# AS3364_DG412_bus_mixer_v1_4.net
KiCad netlist of a schematic drawn in EAGLE
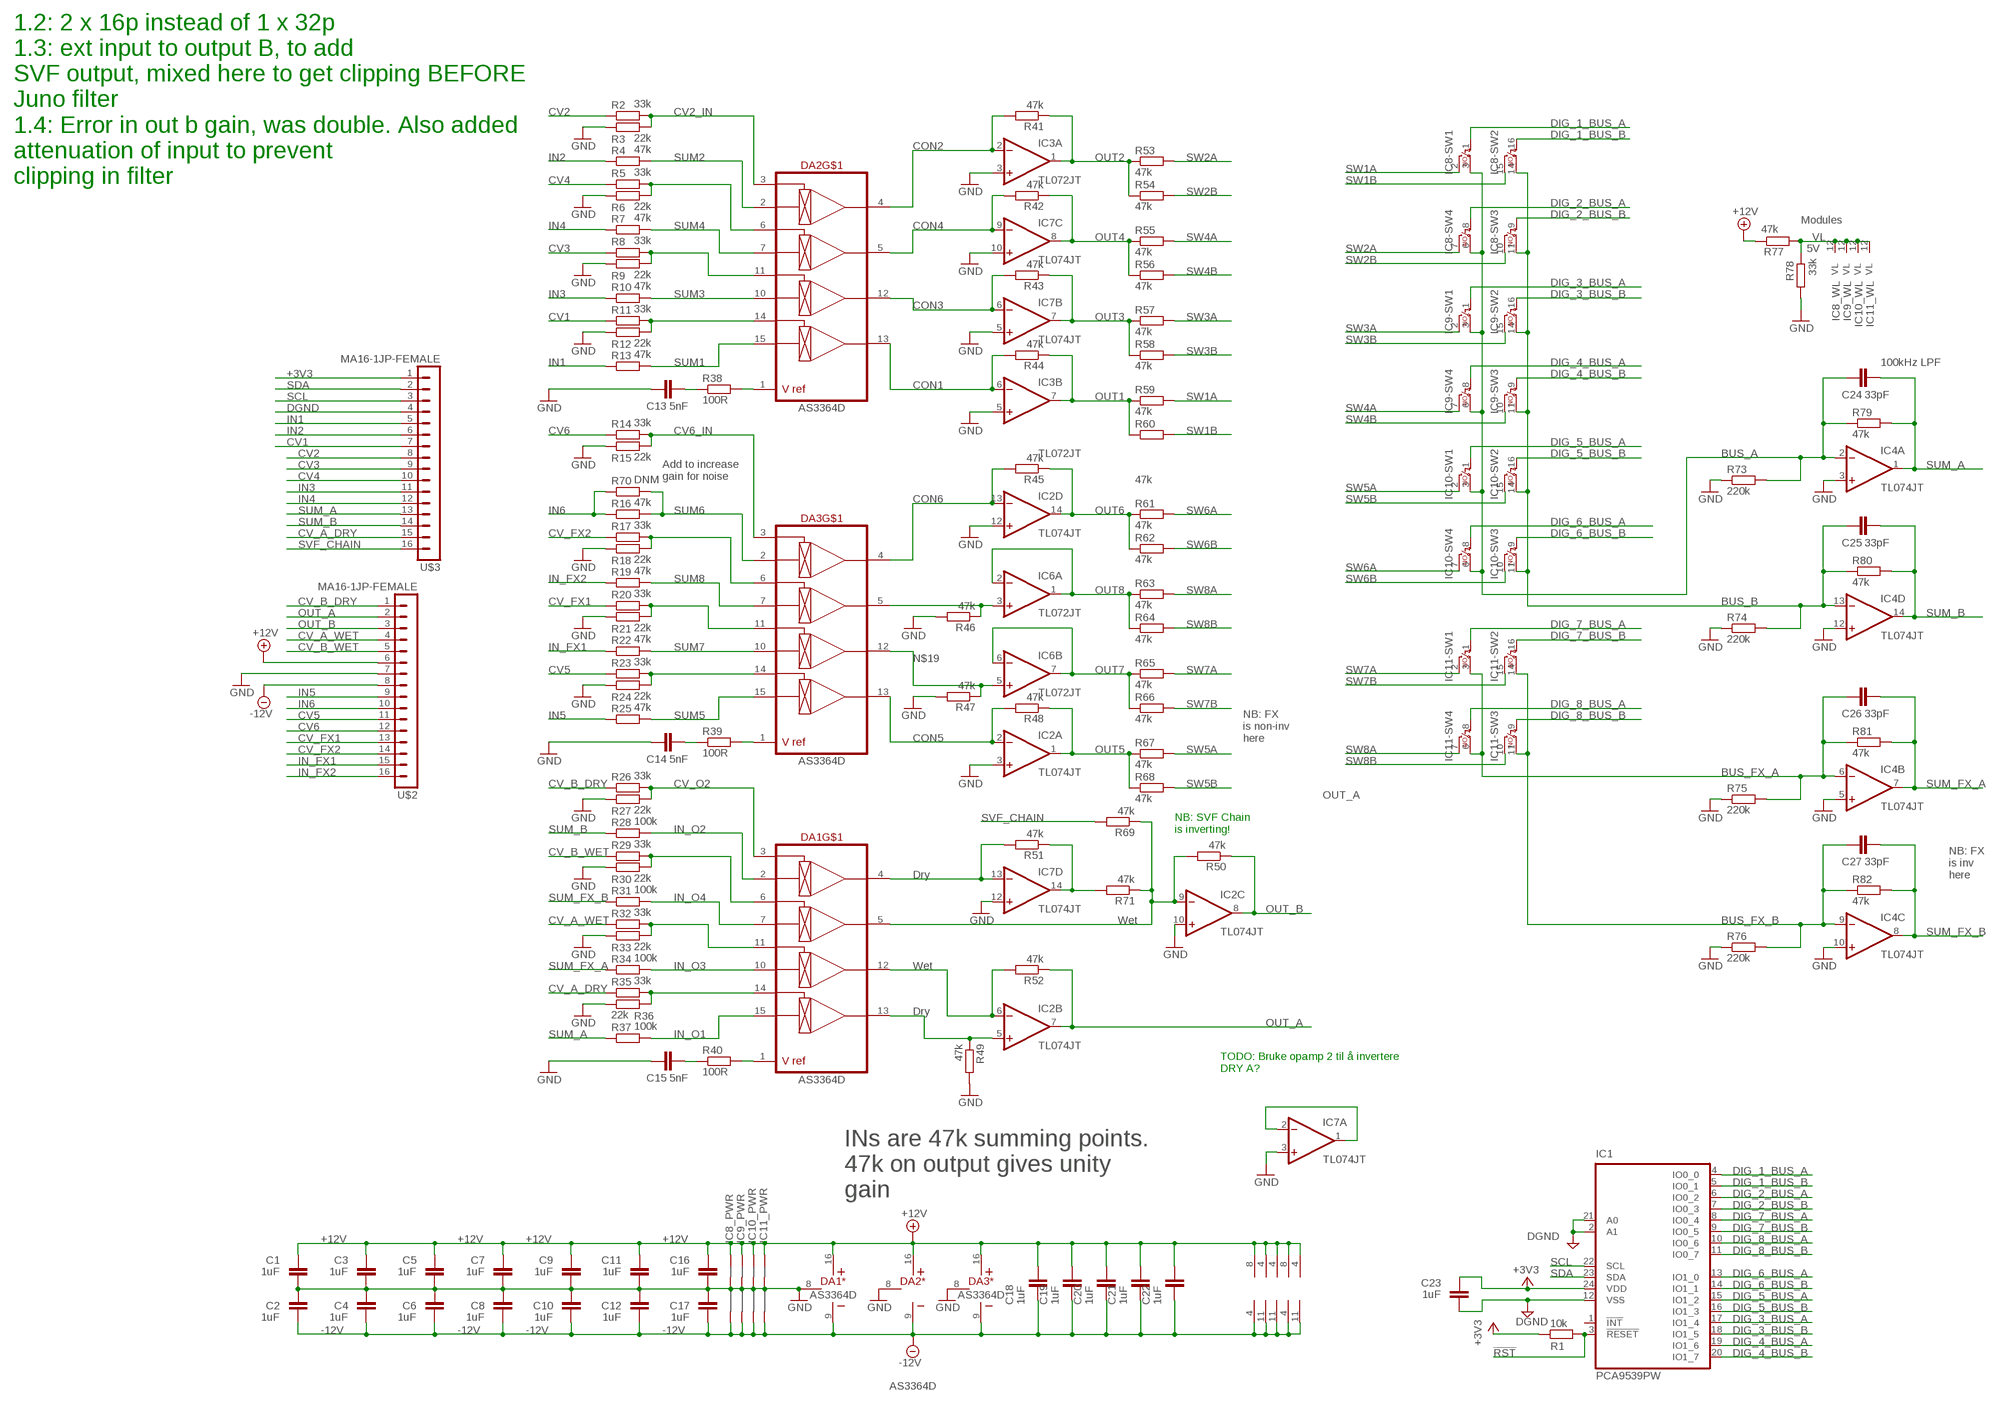
[diagram p0: schematic, sheet 1]

(export (version "E")
  (design (tool "Eeschema 10.0.6"))
  (components
    (comp (ref "C1")
      (value "1uF")
      (footprint "eagle-import:C0402-J")
      (libsource (lib "eagle-import") (part "C-EU-J0402"))
    )
    (comp (ref "C2")
      (value "1uF")
      (footprint "eagle-import:C0402-J")
      (libsource (lib "eagle-import") (part "C-EU-J0402"))
    )
    (comp (ref "C3")
      (value "1uF")
      (footprint "eagle-import:C0402-J")
      (libsource (lib "eagle-import") (part "C-EU-J0402"))
    )
    (comp (ref "C4")
      (value "1uF")
      (footprint "eagle-import:C0402-J")
      (libsource (lib "eagle-import") (part "C-EU-J0402"))
    )
    (comp (ref "C5")
      (value "1uF")
      (footprint "eagle-import:C0402-J")
      (libsource (lib "eagle-import") (part "C-EU-J0402"))
    )
    (comp (ref "C6")
      (value "1uF")
      (footprint "eagle-import:C0402-J")
      (libsource (lib "eagle-import") (part "C-EU-J0402"))
    )
    (comp (ref "C7")
      (value "1uF")
      (footprint "eagle-import:C0402-J")
      (libsource (lib "eagle-import") (part "C-EU-J0402"))
    )
    (comp (ref "C8")
      (value "1uF")
      (footprint "eagle-import:C0402-J")
      (libsource (lib "eagle-import") (part "C-EU-J0402"))
    )
    (comp (ref "C9")
      (value "1uF")
      (footprint "eagle-import:C0402-J")
      (libsource (lib "eagle-import") (part "C-EU-J0402"))
    )
    (comp (ref "C10")
      (value "1uF")
      (footprint "eagle-import:C0402-J")
      (libsource (lib "eagle-import") (part "C-EU-J0402"))
    )
    (comp (ref "C11")
      (value "1uF")
      (footprint "eagle-import:C0402-J")
      (libsource (lib "eagle-import") (part "C-EU-J0402"))
    )
    (comp (ref "C12")
      (value "1uF")
      (footprint "eagle-import:C0402-J")
      (libsource (lib "eagle-import") (part "C-EU-J0402"))
    )
    (comp (ref "C13")
      (value "5nF")
      (footprint "eagle-import:C0402-J")
      (libsource (lib "eagle-import") (part "C-EU-J0402"))
    )
    (comp (ref "C14")
      (value "5nF")
      (footprint "eagle-import:C0402-J")
      (libsource (lib "eagle-import") (part "C-EU-J0402"))
    )
    (comp (ref "C15")
      (value "5nF")
      (footprint "eagle-import:C0402-J")
      (libsource (lib "eagle-import") (part "C-EU-J0402"))
    )
    (comp (ref "C16")
      (value "1uF")
      (footprint "eagle-import:C0402-J")
      (libsource (lib "eagle-import") (part "C-EU-J0402"))
    )
    (comp (ref "C17")
      (value "1uF")
      (footprint "eagle-import:C0402-J")
      (libsource (lib "eagle-import") (part "C-EU-J0402"))
    )
    (comp (ref "C18")
      (value "1uF")
      (footprint "eagle-import:C0402")
      (libsource (lib "eagle-import") (part "C-EUC0402"))
    )
    (comp (ref "C19")
      (value "1uF")
      (footprint "eagle-import:C0402")
      (libsource (lib "eagle-import") (part "C-EUC0402"))
    )
    (comp (ref "C20")
      (value "1uF")
      (footprint "eagle-import:C0402")
      (libsource (lib "eagle-import") (part "C-EUC0402"))
    )
    (comp (ref "C21")
      (value "1uF")
      (footprint "eagle-import:C0402")
      (libsource (lib "eagle-import") (part "C-EUC0402"))
    )
    (comp (ref "C22")
      (value "1uF")
      (footprint "eagle-import:C0402")
      (libsource (lib "eagle-import") (part "C-EUC0402"))
    )
    (comp (ref "C23")
      (value "1uF")
      (footprint "eagle-import:C0402")
      (libsource (lib "eagle-import") (part "C-EUC0402"))
    )
    (comp (ref "C24")
      (value "33pF")
      (footprint "eagle-import:C0402-J")
      (libsource (lib "eagle-import") (part "C-EU-J0402"))
    )
    (comp (ref "C25")
      (value "33pF")
      (footprint "eagle-import:C0402-J")
      (libsource (lib "eagle-import") (part "C-EU-J0402"))
    )
    (comp (ref "C26")
      (value "33pF")
      (footprint "eagle-import:C0402-J")
      (libsource (lib "eagle-import") (part "C-EU-J0402"))
    )
    (comp (ref "C27")
      (value "33pF")
      (footprint "eagle-import:C0402-J")
      (libsource (lib "eagle-import") (part "C-EU-J0402"))
    )
    (comp (ref "DA1")
      (value "AS3364D")
      (footprint "eagle-import:DIL16J")
      (libsource (lib "eagle-import") (part "AS3364D"))
    )
    (comp (ref "DA2")
      (value "AS3364D")
      (footprint "eagle-import:DIL16J")
      (libsource (lib "eagle-import") (part "AS3364D"))
    )
    (comp (ref "DA3")
      (value "AS3364D")
      (footprint "eagle-import:DIL16J")
      (libsource (lib "eagle-import") (part "AS3364D"))
    )
    (comp (ref "IC1")
      (value "PCA9539PW")
      (footprint "eagle-import:TSSOP24J")
      (libsource (lib "eagle-import") (part "PCA9539PW"))
    )
    (comp (ref "IC2")
      (value "TL074JT")
      (footprint "eagle-import:TSSOP14J")
      (libsource (lib "eagle-import") (part "TL074JT"))
    )
    (comp (ref "IC3")
      (value "TL072JT")
      (footprint "eagle-import:TSSOP8J")
      (libsource (lib "eagle-import") (part "TL072JT"))
    )
    (comp (ref "IC4")
      (value "TL074JT")
      (footprint "eagle-import:TSSOP14J")
      (libsource (lib "eagle-import") (part "TL074JT"))
    )
    (comp (ref "IC6")
      (value "TL072JT")
      (footprint "eagle-import:TSSOP8J")
      (libsource (lib "eagle-import") (part "TL072JT"))
    )
    (comp (ref "IC7")
      (value "TL074JT")
      (footprint "eagle-import:TSSOP14J")
      (libsource (lib "eagle-import") (part "TL074JT"))
    )
    (comp (ref "IC8")
      (value "DG412-J")
      (footprint "eagle-import:DIL16J")
      (libsource (lib "eagle-import") (part "DG412-J"))
    )
    (comp (ref "IC9")
      (value "DG412-J")
      (footprint "eagle-import:DIL16J")
      (libsource (lib "eagle-import") (part "DG412-J"))
    )
    (comp (ref "IC10")
      (value "DG412-J")
      (footprint "eagle-import:DIL16J")
      (libsource (lib "eagle-import") (part "DG412-J"))
    )
    (comp (ref "IC11")
      (value "DG412-J")
      (footprint "eagle-import:DIL16J")
      (libsource (lib "eagle-import") (part "DG412-J"))
    )
    (comp (ref "R1")
      (value "10k")
      (footprint "eagle-import:R0402")
      (libsource (lib "eagle-import") (part "R-EU_R0402"))
    )
    (comp (ref "R2")
      (value "33k")
      (footprint "eagle-import:R0402")
      (libsource (lib "eagle-import") (part "R-EU_R0402"))
    )
    (comp (ref "R3")
      (value "22k")
      (footprint "eagle-import:R0402")
      (libsource (lib "eagle-import") (part "R-EU_R0402"))
    )
    (comp (ref "R4")
      (value "47k")
      (footprint "eagle-import:R0402")
      (libsource (lib "eagle-import") (part "R-EU_R0402"))
    )
    (comp (ref "R5")
      (value "33k")
      (footprint "eagle-import:R0402")
      (libsource (lib "eagle-import") (part "R-EU_R0402"))
    )
    (comp (ref "R6")
      (value "22k")
      (footprint "eagle-import:R0402")
      (libsource (lib "eagle-import") (part "R-EU_R0402"))
    )
    (comp (ref "R7")
      (value "47k")
      (footprint "eagle-import:R0402")
      (libsource (lib "eagle-import") (part "R-EU_R0402"))
    )
    (comp (ref "R8")
      (value "33k")
      (footprint "eagle-import:R0402")
      (libsource (lib "eagle-import") (part "R-EU_R0402"))
    )
    (comp (ref "R9")
      (value "22k")
      (footprint "eagle-import:R0402")
      (libsource (lib "eagle-import") (part "R-EU_R0402"))
    )
    (comp (ref "R10")
      (value "47k")
      (footprint "eagle-import:R0402")
      (libsource (lib "eagle-import") (part "R-EU_R0402"))
    )
    (comp (ref "R11")
      (value "33k")
      (footprint "eagle-import:R0402")
      (libsource (lib "eagle-import") (part "R-EU_R0402"))
    )
    (comp (ref "R12")
      (value "22k")
      (footprint "eagle-import:R0402")
      (libsource (lib "eagle-import") (part "R-EU_R0402"))
    )
    (comp (ref "R13")
      (value "47k")
      (footprint "eagle-import:R0402")
      (libsource (lib "eagle-import") (part "R-EU_R0402"))
    )
    (comp (ref "R14")
      (value "33k")
      (footprint "eagle-import:R0402")
      (libsource (lib "eagle-import") (part "R-EU_R0402"))
    )
    (comp (ref "R15")
      (value "22k")
      (footprint "eagle-import:R0402")
      (libsource (lib "eagle-import") (part "R-EU_R0402"))
    )
    (comp (ref "R16")
      (value "47k")
      (footprint "eagle-import:R0402")
      (libsource (lib "eagle-import") (part "R-EU_R0402"))
    )
    (comp (ref "R17")
      (value "33k")
      (footprint "eagle-import:R0402")
      (libsource (lib "eagle-import") (part "R-EU_R0402"))
    )
    (comp (ref "R18")
      (value "22k")
      (footprint "eagle-import:R0402")
      (libsource (lib "eagle-import") (part "R-EU_R0402"))
    )
    (comp (ref "R19")
      (value "47k")
      (footprint "eagle-import:R0402")
      (libsource (lib "eagle-import") (part "R-EU_R0402"))
    )
    (comp (ref "R20")
      (value "33k")
      (footprint "eagle-import:R0402")
      (libsource (lib "eagle-import") (part "R-EU_R0402"))
    )
    (comp (ref "R21")
      (value "22k")
      (footprint "eagle-import:R0402")
      (libsource (lib "eagle-import") (part "R-EU_R0402"))
    )
    (comp (ref "R22")
      (value "47k")
      (footprint "eagle-import:R0402")
      (libsource (lib "eagle-import") (part "R-EU_R0402"))
    )
    (comp (ref "R23")
      (value "33k")
      (footprint "eagle-import:R0402")
      (libsource (lib "eagle-import") (part "R-EU_R0402"))
    )
    (comp (ref "R24")
      (value "22k")
      (footprint "eagle-import:R0402")
      (libsource (lib "eagle-import") (part "R-EU_R0402"))
    )
    (comp (ref "R25")
      (value "47k")
      (footprint "eagle-import:R0402")
      (libsource (lib "eagle-import") (part "R-EU_R0402"))
    )
    (comp (ref "R26")
      (value "33k")
      (footprint "eagle-import:R0402")
      (libsource (lib "eagle-import") (part "R-EU_R0402"))
    )
    (comp (ref "R27")
      (value "22k")
      (footprint "eagle-import:R0402")
      (libsource (lib "eagle-import") (part "R-EU_R0402"))
    )
    (comp (ref "R28")
      (value "100k")
      (footprint "eagle-import:R0402")
      (libsource (lib "eagle-import") (part "R-EU_R0402"))
    )
    (comp (ref "R29")
      (value "33k")
      (footprint "eagle-import:R0402")
      (libsource (lib "eagle-import") (part "R-EU_R0402"))
    )
    (comp (ref "R30")
      (value "22k")
      (footprint "eagle-import:R0402")
      (libsource (lib "eagle-import") (part "R-EU_R0402"))
    )
    (comp (ref "R31")
      (value "100k")
      (footprint "eagle-import:R0402")
      (libsource (lib "eagle-import") (part "R-EU_R0402"))
    )
    (comp (ref "R32")
      (value "33k")
      (footprint "eagle-import:R0402")
      (libsource (lib "eagle-import") (part "R-EU_R0402"))
    )
    (comp (ref "R33")
      (value "22k")
      (footprint "eagle-import:R0402")
      (libsource (lib "eagle-import") (part "R-EU_R0402"))
    )
    (comp (ref "R34")
      (value "100k")
      (footprint "eagle-import:R0402")
      (libsource (lib "eagle-import") (part "R-EU_R0402"))
    )
    (comp (ref "R35")
      (value "33k")
      (footprint "eagle-import:R0402")
      (libsource (lib "eagle-import") (part "R-EU_R0402"))
    )
    (comp (ref "R36")
      (value "22k")
      (footprint "eagle-import:R0402")
      (libsource (lib "eagle-import") (part "R-EU_R0402"))
    )
    (comp (ref "R37")
      (value "100k")
      (footprint "eagle-import:R0402")
      (libsource (lib "eagle-import") (part "R-EU_R0402"))
    )
    (comp (ref "R38")
      (value "100R")
      (footprint "eagle-import:R0402")
      (libsource (lib "eagle-import") (part "R-EU_R0402"))
    )
    (comp (ref "R39")
      (value "100R")
      (footprint "eagle-import:R0402")
      (libsource (lib "eagle-import") (part "R-EU_R0402"))
    )
    (comp (ref "R40")
      (value "100R")
      (footprint "eagle-import:R0402")
      (libsource (lib "eagle-import") (part "R-EU_R0402"))
    )
    (comp (ref "R41")
      (value "47k")
      (footprint "eagle-import:R0402")
      (libsource (lib "eagle-import") (part "R-EU_R0402"))
    )
    (comp (ref "R42")
      (value "47k")
      (footprint "eagle-import:R0402")
      (libsource (lib "eagle-import") (part "R-EU_R0402"))
    )
    (comp (ref "R43")
      (value "47k")
      (footprint "eagle-import:R0402")
      (libsource (lib "eagle-import") (part "R-EU_R0402"))
    )
    (comp (ref "R44")
      (value "47k")
      (footprint "eagle-import:R0402")
      (libsource (lib "eagle-import") (part "R-EU_R0402"))
    )
    (comp (ref "R45")
      (value "47k")
      (footprint "eagle-import:R0402")
      (libsource (lib "eagle-import") (part "R-EU_R0402"))
    )
    (comp (ref "R46")
      (value "47k")
      (footprint "eagle-import:R0402")
      (libsource (lib "eagle-import") (part "R-EU_R0402"))
    )
    (comp (ref "R47")
      (value "47k")
      (footprint "eagle-import:R0402")
      (libsource (lib "eagle-import") (part "R-EU_R0402"))
    )
    (comp (ref "R48")
      (value "47k")
      (footprint "eagle-import:R0402")
      (libsource (lib "eagle-import") (part "R-EU_R0402"))
    )
    (comp (ref "R49")
      (value "47k")
      (footprint "eagle-import:R0402")
      (libsource (lib "eagle-import") (part "R-EU_R0402"))
    )
    (comp (ref "R50")
      (value "47k")
      (footprint "eagle-import:R0402")
      (libsource (lib "eagle-import") (part "R-EU_R0402"))
    )
    (comp (ref "R51")
      (value "47k")
      (footprint "eagle-import:R0402")
      (libsource (lib "eagle-import") (part "R-EU_R0402"))
    )
    (comp (ref "R52")
      (value "47k")
      (footprint "eagle-import:R0402")
      (libsource (lib "eagle-import") (part "R-EU_R0402"))
    )
    (comp (ref "R53")
      (value "47k")
      (footprint "eagle-import:R0402")
      (libsource (lib "eagle-import") (part "R-EU_R0402"))
    )
    (comp (ref "R54")
      (value "47k")
      (footprint "eagle-import:R0402")
      (libsource (lib "eagle-import") (part "R-EU_R0402"))
    )
    (comp (ref "R55")
      (value "47k")
      (footprint "eagle-import:R0402")
      (libsource (lib "eagle-import") (part "R-EU_R0402"))
    )
    (comp (ref "R56")
      (value "47k")
      (footprint "eagle-import:R0402")
      (libsource (lib "eagle-import") (part "R-EU_R0402"))
    )
    (comp (ref "R57")
      (value "47k")
      (footprint "eagle-import:R0402")
      (libsource (lib "eagle-import") (part "R-EU_R0402"))
    )
    (comp (ref "R58")
      (value "47k")
      (footprint "eagle-import:R0402")
      (libsource (lib "eagle-import") (part "R-EU_R0402"))
    )
    (comp (ref "R59")
      (value "47k")
      (footprint "eagle-import:R0402")
      (libsource (lib "eagle-import") (part "R-EU_R0402"))
    )
    (comp (ref "R60")
      (value "47k")
      (footprint "eagle-import:R0402")
      (libsource (lib "eagle-import") (part "R-EU_R0402"))
    )
    (comp (ref "R61")
      (value "47k")
      (footprint "eagle-import:R0402")
      (libsource (lib "eagle-import") (part "R-EU_R0402"))
    )
    (comp (ref "R62")
      (value "47k")
      (footprint "eagle-import:R0402")
      (libsource (lib "eagle-import") (part "R-EU_R0402"))
    )
    (comp (ref "R63")
      (value "47k")
      (footprint "eagle-import:R0402")
      (libsource (lib "eagle-import") (part "R-EU_R0402"))
    )
    (comp (ref "R64")
      (value "47k")
      (footprint "eagle-import:R0402")
      (libsource (lib "eagle-import") (part "R-EU_R0402"))
    )
    (comp (ref "R65")
      (value "47k")
      (footprint "eagle-import:R0402")
      (libsource (lib "eagle-import") (part "R-EU_R0402"))
    )
    (comp (ref "R66")
      (value "47k")
      (footprint "eagle-import:R0402")
      (libsource (lib "eagle-import") (part "R-EU_R0402"))
    )
    (comp (ref "R67")
      (value "47k")
      (footprint "eagle-import:R0402")
      (libsource (lib "eagle-import") (part "R-EU_R0402"))
    )
    (comp (ref "R68")
      (value "47k")
      (footprint "eagle-import:R0402")
      (libsource (lib "eagle-import") (part "R-EU_R0402"))
    )
    (comp (ref "R69")
      (value "47k")
      (footprint "eagle-import:R0402")
      (libsource (lib "eagle-import") (part "R-EU_R0402"))
    )
    (comp (ref "R70")
      (value "DNM")
      (footprint "eagle-import:R0805")
      (libsource (lib "eagle-import") (part "R-EU_R0805"))
    )
    (comp (ref "R71")
      (value "47k")
      (footprint "eagle-import:R0402")
      (libsource (lib "eagle-import") (part "R-EU_R0402"))
    )
    (comp (ref "R73")
      (value "220k")
      (footprint "eagle-import:R0603")
      (libsource (lib "eagle-import") (part "R-EU_R0603"))
    )
    (comp (ref "R74")
      (value "220k")
      (footprint "eagle-import:R0603")
      (libsource (lib "eagle-import") (part "R-EU_R0603"))
    )
    (comp (ref "R75")
      (value "220k")
      (footprint "eagle-import:R0603")
      (libsource (lib "eagle-import") (part "R-EU_R0603"))
    )
    (comp (ref "R76")
      (value "220k")
      (footprint "eagle-import:R0603")
      (libsource (lib "eagle-import") (part "R-EU_R0603"))
    )
    (comp (ref "R77")
      (value "47k")
      (footprint "eagle-import:R0402")
      (libsource (lib "eagle-import") (part "R-EU_R0402"))
    )
    (comp (ref "R78")
      (value "33k")
      (footprint "eagle-import:R0402")
      (libsource (lib "eagle-import") (part "R-EU_R0402"))
    )
    (comp (ref "R79")
      (value "47k")
      (footprint "eagle-import:R0402")
      (libsource (lib "eagle-import") (part "R-EU_R0402"))
    )
    (comp (ref "R80")
      (value "47k")
      (footprint "eagle-import:R0402")
      (libsource (lib "eagle-import") (part "R-EU_R0402"))
    )
    (comp (ref "R81")
      (value "47k")
      (footprint "eagle-import:R0402")
      (libsource (lib "eagle-import") (part "R-EU_R0402"))
    )
    (comp (ref "R82")
      (value "47k")
      (footprint "eagle-import:R0402")
      (libsource (lib "eagle-import") (part "R-EU_R0402"))
    )
    (comp (ref "U$2")
      (value "MA16-1JP-FEMALE")
      (footprint "eagle-import:SIP-PIN16-1J")
      (libsource (lib "eagle-import") (part "MA16-1JP"))
    )
    (comp (ref "U$3")
      (value "MA16-1JP-FEMALE")
      (footprint "eagle-import:SIP-PIN16-1J")
      (libsource (lib "eagle-import") (part "MA16-1JP"))
    )
  )
  (nets
    (net (code "1") (name "+3V3") (class "Default")
      (node (ref "C23") (pin "2") (pinfunction "2_2") (pintype "passive"))
      (node (ref "IC1") (pin "24") (pinfunction "VDD_24") (pintype "power_in"))
      (node (ref "R1") (pin "1") (pinfunction "1_1") (pintype "passive"))
      (node (ref "U$3") (pin "1") (pinfunction "1_1") (pintype "passive"))
    )
    (net (code "2") (name "+12V") (class "Default")
      (node (ref "C1") (pin "2") (pinfunction "2_2") (pintype "passive"))
      (node (ref "C11") (pin "2") (pinfunction "2_2") (pintype "passive"))
      (node (ref "C16") (pin "2") (pinfunction "2_2") (pintype "passive"))
      (node (ref "C18") (pin "2") (pinfunction "2_2") (pintype "passive"))
      (node (ref "C19") (pin "2") (pinfunction "2_2") (pintype "passive"))
      (node (ref "C20") (pin "2") (pinfunction "2_2") (pintype "passive"))
      (node (ref "C21") (pin "2") (pinfunction "2_2") (pintype "passive"))
      (node (ref "C22") (pin "2") (pinfunction "2_2") (pintype "passive"))
      (node (ref "C3") (pin "2") (pinfunction "2_2") (pintype "passive"))
      (node (ref "C5") (pin "2") (pinfunction "2_2") (pintype "passive"))
      (node (ref "C7") (pin "2") (pinfunction "2_2") (pintype "passive"))
      (node (ref "C9") (pin "2") (pinfunction "2_2") (pintype "passive"))
      (node (ref "DA1") (pin "16") (pinfunction "V+_16") (pintype "power_in"))
      (node (ref "DA2") (pin "16") (pinfunction "V+_16") (pintype "power_in"))
      (node (ref "DA3") (pin "16") (pinfunction "V+_16") (pintype "power_in"))
      (node (ref "IC10") (pin "13") (pinfunction "+15V_13") (pintype "power_in"))
      (node (ref "IC11") (pin "13") (pinfunction "+15V_13") (pintype "power_in"))
      (node (ref "IC2") (pin "4") (pinfunction "V+_4") (pintype "power_in"))
      (node (ref "IC3") (pin "8") (pinfunction "V+_8") (pintype "power_in"))
      (node (ref "IC4") (pin "4") (pinfunction "V+_4") (pintype "power_in"))
      (node (ref "IC6") (pin "8") (pinfunction "V+_8") (pintype "power_in"))
      (node (ref "IC7") (pin "4") (pinfunction "V+_4") (pintype "power_in"))
      (node (ref "IC8") (pin "13") (pinfunction "+15V_13") (pintype "power_in"))
      (node (ref "IC9") (pin "13") (pinfunction "+15V_13") (pintype "power_in"))
      (node (ref "R77") (pin "1") (pinfunction "1_1") (pintype "passive"))
      (node (ref "U$2") (pin "6") (pinfunction "6_6") (pintype "passive"))
    )
    (net (code "3") (name "-12V") (class "Default")
      (node (ref "C10") (pin "1") (pinfunction "1_1") (pintype "passive"))
      (node (ref "C12") (pin "1") (pinfunction "1_1") (pintype "passive"))
      (node (ref "C17") (pin "1") (pinfunction "1_1") (pintype "passive"))
      (node (ref "C18") (pin "1") (pinfunction "1_1") (pintype "passive"))
      (node (ref "C19") (pin "1") (pinfunction "1_1") (pintype "passive"))
      (node (ref "C2") (pin "1") (pinfunction "1_1") (pintype "passive"))
      (node (ref "C20") (pin "1") (pinfunction "1_1") (pintype "passive"))
      (node (ref "C21") (pin "1") (pinfunction "1_1") (pintype "passive"))
      (node (ref "C22") (pin "1") (pinfunction "1_1") (pintype "passive"))
      (node (ref "C4") (pin "1") (pinfunction "1_1") (pintype "passive"))
      (node (ref "C6") (pin "1") (pinfunction "1_1") (pintype "passive"))
      (node (ref "C8") (pin "1") (pinfunction "1_1") (pintype "passive"))
      (node (ref "DA1") (pin "9") (pinfunction "V-_9") (pintype "power_in"))
      (node (ref "DA2") (pin "9") (pinfunction "V-_9") (pintype "power_in"))
      (node (ref "DA3") (pin "9") (pinfunction "V-_9") (pintype "power_in"))
      (node (ref "IC10") (pin "4") (pinfunction "-15V_4") (pintype "power_in"))
      (node (ref "IC11") (pin "4") (pinfunction "-15V_4") (pintype "power_in"))
      (node (ref "IC2") (pin "11") (pinfunction "V-_11") (pintype "power_in"))
      (node (ref "IC3") (pin "4") (pinfunction "V-_4") (pintype "power_in"))
      (node (ref "IC4") (pin "11") (pinfunction "V-_11") (pintype "power_in"))
      (node (ref "IC6") (pin "4") (pinfunction "V-_4") (pintype "power_in"))
      (node (ref "IC7") (pin "11") (pinfunction "V-_11") (pintype "power_in"))
      (node (ref "IC8") (pin "4") (pinfunction "-15V_4") (pintype "power_in"))
      (node (ref "IC9") (pin "4") (pinfunction "-15V_4") (pintype "power_in"))
      (node (ref "U$2") (pin "8") (pinfunction "8_8") (pintype "passive"))
    )
    (net (code "4") (name "/BUS_A") (class "Default")
      (node (ref "C24") (pin "1") (pinfunction "1_1") (pintype "passive"))
      (node (ref "IC10") (pin "3") (pinfunction "S_3") (pintype "bidirectional"))
      (node (ref "IC10") (pin "6") (pinfunction "S_6") (pintype "bidirectional"))
      (node (ref "IC4") (pin "2") (pinfunction "-IN_2") (pintype "input"))
      (node (ref "IC8") (pin "3") (pinfunction "S_3") (pintype "bidirectional"))
      (node (ref "IC8") (pin "6") (pinfunction "S_6") (pintype "bidirectional"))
      (node (ref "IC9") (pin "3") (pinfunction "S_3") (pintype "bidirectional"))
      (node (ref "IC9") (pin "6") (pinfunction "S_6") (pintype "bidirectional"))
      (node (ref "R73") (pin "2") (pinfunction "2_2") (pintype "passive"))
      (node (ref "R79") (pin "1") (pinfunction "1_1") (pintype "passive"))
    )
    (net (code "5") (name "/BUS_B") (class "Default")
      (node (ref "C25") (pin "1") (pinfunction "1_1") (pintype "passive"))
      (node (ref "IC10") (pin "11") (pinfunction "S_11") (pintype "bidirectional"))
      (node (ref "IC10") (pin "14") (pinfunction "S_14") (pintype "bidirectional"))
      (node (ref "IC4") (pin "13") (pinfunction "-IN_13") (pintype "input"))
      (node (ref "IC8") (pin "11") (pinfunction "S_11") (pintype "bidirectional"))
      (node (ref "IC8") (pin "14") (pinfunction "S_14") (pintype "bidirectional"))
      (node (ref "IC9") (pin "11") (pinfunction "S_11") (pintype "bidirectional"))
      (node (ref "IC9") (pin "14") (pinfunction "S_14") (pintype "bidirectional"))
      (node (ref "R74") (pin "2") (pinfunction "2_2") (pintype "passive"))
      (node (ref "R80") (pin "1") (pinfunction "1_1") (pintype "passive"))
    )
    (net (code "6") (name "/BUS_FX_A") (class "Default")
      (node (ref "C26") (pin "1") (pinfunction "1_1") (pintype "passive"))
      (node (ref "IC11") (pin "3") (pinfunction "S_3") (pintype "bidirectional"))
      (node (ref "IC11") (pin "6") (pinfunction "S_6") (pintype "bidirectional"))
      (node (ref "IC4") (pin "6") (pinfunction "-IN_6") (pintype "input"))
      (node (ref "R75") (pin "2") (pinfunction "2_2") (pintype "passive"))
      (node (ref "R81") (pin "1") (pinfunction "1_1") (pintype "passive"))
    )
    (net (code "7") (name "/BUS_FX_B") (class "Default")
      (node (ref "C27") (pin "1") (pinfunction "1_1") (pintype "passive"))
      (node (ref "IC11") (pin "11") (pinfunction "S_11") (pintype "bidirectional"))
      (node (ref "IC11") (pin "14") (pinfunction "S_14") (pintype "bidirectional"))
      (node (ref "IC4") (pin "9") (pinfunction "-IN_9") (pintype "input"))
      (node (ref "R76") (pin "2") (pinfunction "2_2") (pintype "passive"))
      (node (ref "R82") (pin "1") (pinfunction "1_1") (pintype "passive"))
    )
    (net (code "8") (name "/CON1") (class "Default")
      (node (ref "DA2") (pin "13") (pinfunction "OUT4_13") (pintype "output"))
      (node (ref "IC3") (pin "6") (pinfunction "-IN_6") (pintype "input"))
      (node (ref "R44") (pin "2") (pinfunction "2_2") (pintype "passive"))
    )
    (net (code "9") (name "/CON2") (class "Default")
      (node (ref "DA2") (pin "4") (pinfunction "OUT1_4") (pintype "output"))
      (node (ref "IC3") (pin "2") (pinfunction "-IN_2") (pintype "input"))
      (node (ref "R41") (pin "2") (pinfunction "2_2") (pintype "passive"))
    )
    (net (code "10") (name "/CON3") (class "Default")
      (node (ref "DA2") (pin "12") (pinfunction "OUT3_12") (pintype "output"))
      (node (ref "IC7") (pin "6") (pinfunction "-IN_6") (pintype "input"))
      (node (ref "R43") (pin "2") (pinfunction "2_2") (pintype "passive"))
    )
    (net (code "11") (name "/CON4") (class "Default")
      (node (ref "DA2") (pin "5") (pinfunction "OUT2_5") (pintype "output"))
      (node (ref "IC7") (pin "9") (pinfunction "-IN_9") (pintype "input"))
      (node (ref "R42") (pin "2") (pinfunction "2_2") (pintype "passive"))
    )
    (net (code "12") (name "/CON5") (class "Default")
      (node (ref "DA3") (pin "13") (pinfunction "OUT4_13") (pintype "output"))
      (node (ref "IC2") (pin "2") (pinfunction "-IN_2") (pintype "input"))
      (node (ref "R48") (pin "2") (pinfunction "2_2") (pintype "passive"))
    )
    (net (code "13") (name "/CON6") (class "Default")
      (node (ref "DA3") (pin "4") (pinfunction "OUT1_4") (pintype "output"))
      (node (ref "IC2") (pin "13") (pinfunction "-IN_13") (pintype "input"))
      (node (ref "R45") (pin "2") (pinfunction "2_2") (pintype "passive"))
    )
    (net (code "14") (name "/CV1") (class "Default")
      (node (ref "R11") (pin "1") (pinfunction "1_1") (pintype "passive"))
      (node (ref "U$3") (pin "7") (pinfunction "7_7") (pintype "passive"))
    )
    (net (code "15") (name "/CV2") (class "Default")
      (node (ref "R2") (pin "1") (pinfunction "1_1") (pintype "passive"))
      (node (ref "U$3") (pin "8") (pinfunction "8_8") (pintype "passive"))
    )
    (net (code "16") (name "/CV2_IN") (class "Default")
      (node (ref "DA2") (pin "3") (pinfunction "CV1_3") (pintype "input"))
      (node (ref "R2") (pin "2") (pinfunction "2_2") (pintype "passive"))
      (node (ref "R3") (pin "2") (pinfunction "2_2") (pintype "passive"))
    )
    (net (code "17") (name "/CV3") (class "Default")
      (node (ref "R8") (pin "1") (pinfunction "1_1") (pintype "passive"))
      (node (ref "U$3") (pin "9") (pinfunction "9_9") (pintype "passive"))
    )
    (net (code "18") (name "/CV4") (class "Default")
      (node (ref "R5") (pin "1") (pinfunction "1_1") (pintype "passive"))
      (node (ref "U$3") (pin "10") (pinfunction "10_10") (pintype "passive"))
    )
    (net (code "19") (name "/CV5") (class "Default")
      (node (ref "R23") (pin "1") (pinfunction "1_1") (pintype "passive"))
      (node (ref "U$2") (pin "11") (pinfunction "11_11") (pintype "passive"))
    )
    (net (code "20") (name "/CV6") (class "Default")
      (node (ref "R14") (pin "1") (pinfunction "1_1") (pintype "passive"))
      (node (ref "U$2") (pin "12") (pinfunction "12_12") (pintype "passive"))
    )
    (net (code "21") (name "/CV6_IN") (class "Default")
      (node (ref "DA3") (pin "3") (pinfunction "CV1_3") (pintype "input"))
      (node (ref "R14") (pin "2") (pinfunction "2_2") (pintype "passive"))
      (node (ref "R15") (pin "2") (pinfunction "2_2") (pintype "passive"))
    )
    (net (code "22") (name "/CV_A_DRY") (class "Default")
      (node (ref "R35") (pin "1") (pinfunction "1_1") (pintype "passive"))
      (node (ref "U$3") (pin "15") (pinfunction "15_15") (pintype "passive"))
    )
    (net (code "23") (name "/CV_A_WET") (class "Default")
      (node (ref "R32") (pin "1") (pinfunction "1_1") (pintype "passive"))
      (node (ref "U$2") (pin "4") (pinfunction "4_4") (pintype "passive"))
    )
    (net (code "24") (name "/CV_B_DRY") (class "Default")
      (node (ref "R26") (pin "1") (pinfunction "1_1") (pintype "passive"))
      (node (ref "U$2") (pin "1") (pinfunction "1_1") (pintype "passive"))
    )
    (net (code "25") (name "/CV_B_WET") (class "Default")
      (node (ref "R29") (pin "1") (pinfunction "1_1") (pintype "passive"))
      (node (ref "U$2") (pin "5") (pinfunction "5_5") (pintype "passive"))
    )
    (net (code "26") (name "/CV_FX1") (class "Default")
      (node (ref "R20") (pin "1") (pinfunction "1_1") (pintype "passive"))
      (node (ref "U$2") (pin "13") (pinfunction "13_13") (pintype "passive"))
    )
    (net (code "27") (name "/CV_FX2") (class "Default")
      (node (ref "R17") (pin "1") (pinfunction "1_1") (pintype "passive"))
      (node (ref "U$2") (pin "14") (pinfunction "14_14") (pintype "passive"))
    )
    (net (code "28") (name "/CV_O2") (class "Default")
      (node (ref "DA1") (pin "3") (pinfunction "CV1_3") (pintype "input"))
      (node (ref "R26") (pin "2") (pinfunction "2_2") (pintype "passive"))
      (node (ref "R27") (pin "2") (pinfunction "2_2") (pintype "passive"))
    )
    (net (code "29") (name "/DIG_1_BUS_A") (class "Default")
      (node (ref "IC1") (pin "4") (pinfunction "IO0_0_4") (pintype "bidirectional"))
      (node (ref "IC8") (pin "1") (pinfunction "C_1") (pintype "bidirectional"))
    )
    (net (code "30") (name "/DIG_1_BUS_B") (class "Default")
      (node (ref "IC1") (pin "5") (pinfunction "IO0_1_5") (pintype "bidirectional"))
      (node (ref "IC8") (pin "16") (pinfunction "C_16") (pintype "bidirectional"))
    )
    (net (code "31") (name "/DIG_2_BUS_A") (class "Default")
      (node (ref "IC1") (pin "6") (pinfunction "IO0_2_6") (pintype "bidirectional"))
      (node (ref "IC8") (pin "8") (pinfunction "C_8") (pintype "bidirectional"))
    )
    (net (code "32") (name "/DIG_2_BUS_B") (class "Default")
      (node (ref "IC1") (pin "7") (pinfunction "IO0_3_7") (pintype "bidirectional"))
      (node (ref "IC8") (pin "9") (pinfunction "C_9") (pintype "bidirectional"))
    )
    (net (code "33") (name "/DIG_3_BUS_A") (class "Default")
      (node (ref "IC1") (pin "17") (pinfunction "IO1_4_17") (pintype "bidirectional"))
      (node (ref "IC9") (pin "1") (pinfunction "C_1") (pintype "bidirectional"))
    )
    (net (code "34") (name "/DIG_3_BUS_B") (class "Default")
      (node (ref "IC1") (pin "18") (pinfunction "IO1_5_18") (pintype "bidirectional"))
      (node (ref "IC9") (pin "16") (pinfunction "C_16") (pintype "bidirectional"))
    )
    (net (code "35") (name "/DIG_4_BUS_A") (class "Default")
      (node (ref "IC1") (pin "19") (pinfunction "IO1_6_19") (pintype "bidirectional"))
      (node (ref "IC9") (pin "8") (pinfunction "C_8") (pintype "bidirectional"))
    )
    (net (code "36") (name "/DIG_4_BUS_B") (class "Default")
      (node (ref "IC1") (pin "20") (pinfunction "IO1_7_20") (pintype "bidirectional"))
      (node (ref "IC9") (pin "9") (pinfunction "C_9") (pintype "bidirectional"))
    )
    (net (code "37") (name "/DIG_5_BUS_A") (class "Default")
      (node (ref "IC1") (pin "15") (pinfunction "IO1_2_15") (pintype "bidirectional"))
      (node (ref "IC10") (pin "1") (pinfunction "C_1") (pintype "bidirectional"))
    )
    (net (code "38") (name "/DIG_5_BUS_B") (class "Default")
      (node (ref "IC1") (pin "16") (pinfunction "IO1_3_16") (pintype "bidirectional"))
      (node (ref "IC10") (pin "16") (pinfunction "C_16") (pintype "bidirectional"))
    )
    (net (code "39") (name "/DIG_6_BUS_A") (class "Default")
      (node (ref "IC1") (pin "13") (pinfunction "IO1_0_13") (pintype "bidirectional"))
      (node (ref "IC10") (pin "8") (pinfunction "C_8") (pintype "bidirectional"))
    )
    (net (code "40") (name "/DIG_6_BUS_B") (class "Default")
      (node (ref "IC1") (pin "14") (pinfunction "IO1_1_14") (pintype "bidirectional"))
      (node (ref "IC10") (pin "9") (pinfunction "C_9") (pintype "bidirectional"))
    )
    (net (code "41") (name "/DIG_7_BUS_A") (class "Default")
      (node (ref "IC1") (pin "8") (pinfunction "IO0_4_8") (pintype "bidirectional"))
      (node (ref "IC11") (pin "1") (pinfunction "C_1") (pintype "bidirectional"))
    )
    (net (code "42") (name "/DIG_7_BUS_B") (class "Default")
      (node (ref "IC1") (pin "9") (pinfunction "IO0_5_9") (pintype "bidirectional"))
      (node (ref "IC11") (pin "16") (pinfunction "C_16") (pintype "bidirectional"))
    )
    (net (code "43") (name "/DIG_8_BUS_A") (class "Default")
      (node (ref "IC1") (pin "10") (pinfunction "IO0_6_10") (pintype "bidirectional"))
      (node (ref "IC11") (pin "8") (pinfunction "C_8") (pintype "bidirectional"))
    )
    (net (code "44") (name "/DIG_8_BUS_B") (class "Default")
      (node (ref "IC1") (pin "11") (pinfunction "IO0_7_11") (pintype "bidirectional"))
      (node (ref "IC11") (pin "9") (pinfunction "C_9") (pintype "bidirectional"))
    )
    (net (code "45") (name "/IN1") (class "Default")
      (node (ref "R13") (pin "1") (pinfunction "1_1") (pintype "passive"))
      (node (ref "U$3") (pin "5") (pinfunction "5_5") (pintype "passive"))
    )
    (net (code "46") (name "/IN2") (class "Default")
      (node (ref "R4") (pin "1") (pinfunction "1_1") (pintype "passive"))
      (node (ref "U$3") (pin "6") (pinfunction "6_6") (pintype "passive"))
    )
    (net (code "47") (name "/IN3") (class "Default")
      (node (ref "R10") (pin "1") (pinfunction "1_1") (pintype "passive"))
      (node (ref "U$3") (pin "11") (pinfunction "11_11") (pintype "passive"))
    )
    (net (code "48") (name "/IN4") (class "Default")
      (node (ref "R7") (pin "1") (pinfunction "1_1") (pintype "passive"))
      (node (ref "U$3") (pin "12") (pinfunction "12_12") (pintype "passive"))
    )
    (net (code "49") (name "/IN5") (class "Default")
      (node (ref "R25") (pin "1") (pinfunction "1_1") (pintype "passive"))
      (node (ref "U$2") (pin "9") (pinfunction "9_9") (pintype "passive"))
    )
    (net (code "50") (name "/IN6") (class "Default")
      (node (ref "R16") (pin "1") (pinfunction "1_1") (pintype "passive"))
      (node (ref "R70") (pin "1") (pinfunction "1_1") (pintype "passive"))
      (node (ref "U$2") (pin "10") (pinfunction "10_10") (pintype "passive"))
    )
    (net (code "51") (name "/IN_FX1") (class "Default")
      (node (ref "R22") (pin "1") (pinfunction "1_1") (pintype "passive"))
      (node (ref "U$2") (pin "15") (pinfunction "15_15") (pintype "passive"))
    )
    (net (code "52") (name "/IN_FX2") (class "Default")
      (node (ref "R19") (pin "1") (pinfunction "1_1") (pintype "passive"))
      (node (ref "U$2") (pin "16") (pinfunction "16_16") (pintype "passive"))
    )
    (net (code "53") (name "/IN_O1") (class "Default")
      (node (ref "DA1") (pin "15") (pinfunction "IN4_15") (pintype "input"))
      (node (ref "R37") (pin "2") (pinfunction "2_2") (pintype "passive"))
    )
    (net (code "54") (name "/IN_O2") (class "Default")
      (node (ref "DA1") (pin "2") (pinfunction "IN1_2") (pintype "input"))
      (node (ref "R28") (pin "2") (pinfunction "2_2") (pintype "passive"))
    )
    (net (code "55") (name "/IN_O3") (class "Default")
      (node (ref "DA1") (pin "10") (pinfunction "IN3_10") (pintype "input"))
      (node (ref "R34") (pin "2") (pinfunction "2_2") (pintype "passive"))
    )
    (net (code "56") (name "/IN_O4") (class "Default")
      (node (ref "DA1") (pin "7") (pinfunction "IN2_7") (pintype "input"))
      (node (ref "R31") (pin "2") (pinfunction "2_2") (pintype "passive"))
    )
    (net (code "57") (name "/N$19") (class "Default")
      (node (ref "DA3") (pin "12") (pinfunction "OUT3_12") (pintype "output"))
      (node (ref "IC6") (pin "5") (pinfunction "+IN_5") (pintype "input"))
      (node (ref "R47") (pin "1") (pinfunction "1_1") (pintype "passive"))
    )
    (net (code "58") (name "/OUT1") (class "Default")
      (node (ref "IC3") (pin "7") (pinfunction "OUT_7") (pintype "output"))
      (node (ref "R44") (pin "1") (pinfunction "1_1") (pintype "passive"))
      (node (ref "R59") (pin "1") (pinfunction "1_1") (pintype "passive"))
      (node (ref "R60") (pin "1") (pinfunction "1_1") (pintype "passive"))
    )
    (net (code "59") (name "/OUT2") (class "Default")
      (node (ref "IC3") (pin "1") (pinfunction "OUT_1") (pintype "output"))
      (node (ref "R41") (pin "1") (pinfunction "1_1") (pintype "passive"))
      (node (ref "R53") (pin "1") (pinfunction "1_1") (pintype "passive"))
      (node (ref "R54") (pin "1") (pinfunction "1_1") (pintype "passive"))
    )
    (net (code "60") (name "/OUT3") (class "Default")
      (node (ref "IC7") (pin "7") (pinfunction "OUT_7") (pintype "output"))
      (node (ref "R43") (pin "1") (pinfunction "1_1") (pintype "passive"))
      (node (ref "R57") (pin "1") (pinfunction "1_1") (pintype "passive"))
      (node (ref "R58") (pin "1") (pinfunction "1_1") (pintype "passive"))
    )
    (net (code "61") (name "/OUT4") (class "Default")
      (node (ref "IC7") (pin "8") (pinfunction "OUT_8") (pintype "output"))
      (node (ref "R42") (pin "1") (pinfunction "1_1") (pintype "passive"))
      (node (ref "R55") (pin "1") (pinfunction "1_1") (pintype "passive"))
      (node (ref "R56") (pin "1") (pinfunction "1_1") (pintype "passive"))
    )
    (net (code "62") (name "/OUT5") (class "Default")
      (node (ref "IC2") (pin "1") (pinfunction "OUT_1") (pintype "output"))
      (node (ref "R48") (pin "1") (pinfunction "1_1") (pintype "passive"))
      (node (ref "R67") (pin "1") (pinfunction "1_1") (pintype "passive"))
      (node (ref "R68") (pin "1") (pinfunction "1_1") (pintype "passive"))
    )
    (net (code "63") (name "/OUT6") (class "Default")
      (node (ref "IC2") (pin "14") (pinfunction "OUT_14") (pintype "output"))
      (node (ref "R45") (pin "1") (pinfunction "1_1") (pintype "passive"))
      (node (ref "R61") (pin "1") (pinfunction "1_1") (pintype "passive"))
      (node (ref "R62") (pin "1") (pinfunction "1_1") (pintype "passive"))
    )
    (net (code "64") (name "/OUT7") (class "Default")
      (node (ref "IC6") (pin "6") (pinfunction "-IN_6") (pintype "input"))
      (node (ref "IC6") (pin "7") (pinfunction "OUT_7") (pintype "output"))
      (node (ref "R65") (pin "1") (pinfunction "1_1") (pintype "passive"))
      (node (ref "R66") (pin "1") (pinfunction "1_1") (pintype "passive"))
    )
    (net (code "65") (name "/OUT8") (class "Default")
      (node (ref "IC6") (pin "1") (pinfunction "OUT_1") (pintype "output"))
      (node (ref "IC6") (pin "2") (pinfunction "-IN_2") (pintype "input"))
      (node (ref "R63") (pin "1") (pinfunction "1_1") (pintype "passive"))
      (node (ref "R64") (pin "1") (pinfunction "1_1") (pintype "passive"))
    )
    (net (code "66") (name "/OUT_A") (class "Default")
      (node (ref "IC2") (pin "7") (pinfunction "OUT_7") (pintype "output"))
      (node (ref "R52") (pin "1") (pinfunction "1_1") (pintype "passive"))
      (node (ref "U$2") (pin "2") (pinfunction "2_2") (pintype "passive"))
    )
    (net (code "67") (name "/OUT_B") (class "Default")
      (node (ref "IC2") (pin "8") (pinfunction "OUT_8") (pintype "output"))
      (node (ref "R50") (pin "1") (pinfunction "1_1") (pintype "passive"))
      (node (ref "U$2") (pin "3") (pinfunction "3_3") (pintype "passive"))
    )
    (net (code "68") (name "/SCL") (class "Default")
      (node (ref "IC1") (pin "22") (pinfunction "SCL_22") (pintype "bidirectional"))
      (node (ref "U$3") (pin "3") (pinfunction "3_3") (pintype "passive"))
    )
    (net (code "69") (name "/SDA") (class "Default")
      (node (ref "IC1") (pin "23") (pinfunction "SDA_23") (pintype "bidirectional"))
      (node (ref "U$3") (pin "2") (pinfunction "2_2") (pintype "passive"))
    )
    (net (code "70") (name "/SUM1") (class "Default")
      (node (ref "DA2") (pin "15") (pinfunction "IN4_15") (pintype "input"))
      (node (ref "R13") (pin "2") (pinfunction "2_2") (pintype "passive"))
    )
    (net (code "71") (name "/SUM2") (class "Default")
      (node (ref "DA2") (pin "2") (pinfunction "IN1_2") (pintype "input"))
      (node (ref "R4") (pin "2") (pinfunction "2_2") (pintype "passive"))
    )
    (net (code "72") (name "/SUM3") (class "Default")
      (node (ref "DA2") (pin "10") (pinfunction "IN3_10") (pintype "input"))
      (node (ref "R10") (pin "2") (pinfunction "2_2") (pintype "passive"))
    )
    (net (code "73") (name "/SUM4") (class "Default")
      (node (ref "DA2") (pin "7") (pinfunction "IN2_7") (pintype "input"))
      (node (ref "R7") (pin "2") (pinfunction "2_2") (pintype "passive"))
    )
    (net (code "74") (name "/SUM5") (class "Default")
      (node (ref "DA3") (pin "15") (pinfunction "IN4_15") (pintype "input"))
      (node (ref "R25") (pin "2") (pinfunction "2_2") (pintype "passive"))
    )
    (net (code "75") (name "/SUM6") (class "Default")
      (node (ref "DA3") (pin "2") (pinfunction "IN1_2") (pintype "input"))
      (node (ref "R16") (pin "2") (pinfunction "2_2") (pintype "passive"))
      (node (ref "R70") (pin "2") (pinfunction "2_2") (pintype "passive"))
    )
    (net (code "76") (name "/SUM7") (class "Default")
      (node (ref "DA3") (pin "10") (pinfunction "IN3_10") (pintype "input"))
      (node (ref "R22") (pin "2") (pinfunction "2_2") (pintype "passive"))
    )
    (net (code "77") (name "/SUM8") (class "Default")
      (node (ref "DA3") (pin "7") (pinfunction "IN2_7") (pintype "input"))
      (node (ref "R19") (pin "2") (pinfunction "2_2") (pintype "passive"))
    )
    (net (code "78") (name "/SUM_A") (class "Default")
      (node (ref "C24") (pin "2") (pinfunction "2_2") (pintype "passive"))
      (node (ref "IC4") (pin "1") (pinfunction "OUT_1") (pintype "output"))
      (node (ref "R37") (pin "1") (pinfunction "1_1") (pintype "passive"))
      (node (ref "R79") (pin "2") (pinfunction "2_2") (pintype "passive"))
      (node (ref "U$3") (pin "13") (pinfunction "13_13") (pintype "passive"))
    )
    (net (code "79") (name "/SUM_B") (class "Default")
      (node (ref "C25") (pin "2") (pinfunction "2_2") (pintype "passive"))
      (node (ref "IC4") (pin "14") (pinfunction "OUT_14") (pintype "output"))
      (node (ref "R28") (pin "1") (pinfunction "1_1") (pintype "passive"))
      (node (ref "R80") (pin "2") (pinfunction "2_2") (pintype "passive"))
      (node (ref "U$3") (pin "14") (pinfunction "14_14") (pintype "passive"))
    )
    (net (code "80") (name "/SUM_FX_A") (class "Default")
      (node (ref "C26") (pin "2") (pinfunction "2_2") (pintype "passive"))
      (node (ref "IC4") (pin "7") (pinfunction "OUT_7") (pintype "output"))
      (node (ref "R34") (pin "1") (pinfunction "1_1") (pintype "passive"))
      (node (ref "R81") (pin "2") (pinfunction "2_2") (pintype "passive"))
    )
    (net (code "81") (name "/SUM_FX_B") (class "Default")
      (node (ref "C27") (pin "2") (pinfunction "2_2") (pintype "passive"))
      (node (ref "IC4") (pin "8") (pinfunction "OUT_8") (pintype "output"))
      (node (ref "R31") (pin "1") (pinfunction "1_1") (pintype "passive"))
      (node (ref "R82") (pin "2") (pinfunction "2_2") (pintype "passive"))
    )
    (net (code "82") (name "/SVF_CHAIN") (class "Default")
      (node (ref "R69") (pin "2") (pinfunction "2_2") (pintype "passive"))
      (node (ref "U$3") (pin "16") (pinfunction "16_16") (pintype "passive"))
    )
    (net (code "83") (name "/SW1A") (class "Default")
      (node (ref "IC8") (pin "2") (pinfunction "D_2") (pintype "bidirectional"))
      (node (ref "R59") (pin "2") (pinfunction "2_2") (pintype "passive"))
    )
    (net (code "84") (name "/SW1B") (class "Default")
      (node (ref "IC8") (pin "15") (pinfunction "D_15") (pintype "bidirectional"))
      (node (ref "R60") (pin "2") (pinfunction "2_2") (pintype "passive"))
    )
    (net (code "85") (name "/SW2A") (class "Default")
      (node (ref "IC8") (pin "7") (pinfunction "D_7") (pintype "bidirectional"))
      (node (ref "R53") (pin "2") (pinfunction "2_2") (pintype "passive"))
    )
    (net (code "86") (name "/SW2B") (class "Default")
      (node (ref "IC8") (pin "10") (pinfunction "D_10") (pintype "bidirectional"))
      (node (ref "R54") (pin "2") (pinfunction "2_2") (pintype "passive"))
    )
    (net (code "87") (name "/SW3A") (class "Default")
      (node (ref "IC9") (pin "2") (pinfunction "D_2") (pintype "bidirectional"))
      (node (ref "R57") (pin "2") (pinfunction "2_2") (pintype "passive"))
    )
    (net (code "88") (name "/SW3B") (class "Default")
      (node (ref "IC9") (pin "15") (pinfunction "D_15") (pintype "bidirectional"))
      (node (ref "R58") (pin "2") (pinfunction "2_2") (pintype "passive"))
    )
    (net (code "89") (name "/SW4A") (class "Default")
      (node (ref "IC9") (pin "7") (pinfunction "D_7") (pintype "bidirectional"))
      (node (ref "R55") (pin "2") (pinfunction "2_2") (pintype "passive"))
    )
    (net (code "90") (name "/SW4B") (class "Default")
      (node (ref "IC9") (pin "10") (pinfunction "D_10") (pintype "bidirectional"))
      (node (ref "R56") (pin "2") (pinfunction "2_2") (pintype "passive"))
    )
    (net (code "91") (name "/SW5A") (class "Default")
      (node (ref "IC10") (pin "2") (pinfunction "D_2") (pintype "bidirectional"))
      (node (ref "R67") (pin "2") (pinfunction "2_2") (pintype "passive"))
    )
    (net (code "92") (name "/SW5B") (class "Default")
      (node (ref "IC10") (pin "15") (pinfunction "D_15") (pintype "bidirectional"))
      (node (ref "R68") (pin "2") (pinfunction "2_2") (pintype "passive"))
    )
    (net (code "93") (name "/SW6A") (class "Default")
      (node (ref "IC10") (pin "7") (pinfunction "D_7") (pintype "bidirectional"))
      (node (ref "R61") (pin "2") (pinfunction "2_2") (pintype "passive"))
    )
    (net (code "94") (name "/SW6B") (class "Default")
      (node (ref "IC10") (pin "10") (pinfunction "D_10") (pintype "bidirectional"))
      (node (ref "R62") (pin "2") (pinfunction "2_2") (pintype "passive"))
    )
    (net (code "95") (name "/SW7A") (class "Default")
      (node (ref "IC11") (pin "2") (pinfunction "D_2") (pintype "bidirectional"))
      (node (ref "R65") (pin "2") (pinfunction "2_2") (pintype "passive"))
    )
    (net (code "96") (name "/SW7B") (class "Default")
      (node (ref "IC11") (pin "15") (pinfunction "D_15") (pintype "bidirectional"))
      (node (ref "R66") (pin "2") (pinfunction "2_2") (pintype "passive"))
    )
    (net (code "97") (name "/SW8A") (class "Default")
      (node (ref "IC11") (pin "7") (pinfunction "D_7") (pintype "bidirectional"))
      (node (ref "R63") (pin "2") (pinfunction "2_2") (pintype "passive"))
    )
    (net (code "98") (name "/SW8B") (class "Default")
      (node (ref "IC11") (pin "10") (pinfunction "D_10") (pintype "bidirectional"))
      (node (ref "R64") (pin "2") (pinfunction "2_2") (pintype "passive"))
    )
    (net (code "99") (name "/VL") (class "Default")
      (node (ref "IC10") (pin "12") (pinfunction "VL_12") (pintype "bidirectional"))
      (node (ref "IC11") (pin "12") (pinfunction "VL_12") (pintype "bidirectional"))
      (node (ref "IC8") (pin "12") (pinfunction "VL_12") (pintype "bidirectional"))
      (node (ref "IC9") (pin "12") (pinfunction "VL_12") (pintype "bidirectional"))
      (node (ref "R77") (pin "2") (pinfunction "2_2") (pintype "passive"))
      (node (ref "R78") (pin "1") (pinfunction "1_1") (pintype "passive"))
    )
    (net (code "100") (name "/~{RST}") (class "Default")
      (node (ref "IC1") (pin "3") (pinfunction "~{RESET}_3") (pintype "bidirectional"))
      (node (ref "R1") (pin "2") (pinfunction "2_2") (pintype "passive"))
    )
    (net (code "101") (name "DGND") (class "Default")
      (node (ref "C23") (pin "1") (pinfunction "1_1") (pintype "passive"))
      (node (ref "IC1") (pin "12") (pinfunction "VSS_12") (pintype "power_in"))
      (node (ref "IC1") (pin "2") (pinfunction "A1_2") (pintype "bidirectional"))
      (node (ref "IC1") (pin "21") (pinfunction "A0_21") (pintype "bidirectional"))
      (node (ref "U$3") (pin "4") (pinfunction "4_4") (pintype "passive"))
    )
    (net (code "102") (name "GND") (class "Default")
      (node (ref "C1") (pin "1") (pinfunction "1_1") (pintype "passive"))
      (node (ref "C10") (pin "2") (pinfunction "2_2") (pintype "passive"))
      (node (ref "C11") (pin "1") (pinfunction "1_1") (pintype "passive"))
      (node (ref "C12") (pin "2") (pinfunction "2_2") (pintype "passive"))
      (node (ref "C13") (pin "1") (pinfunction "1_1") (pintype "passive"))
      (node (ref "C14") (pin "1") (pinfunction "1_1") (pintype "passive"))
      (node (ref "C15") (pin "1") (pinfunction "1_1") (pintype "passive"))
      (node (ref "C16") (pin "1") (pinfunction "1_1") (pintype "passive"))
      (node (ref "C17") (pin "2") (pinfunction "2_2") (pintype "passive"))
      (node (ref "C2") (pin "2") (pinfunction "2_2") (pintype "passive"))
      (node (ref "C3") (pin "1") (pinfunction "1_1") (pintype "passive"))
      (node (ref "C4") (pin "2") (pinfunction "2_2") (pintype "passive"))
      (node (ref "C5") (pin "1") (pinfunction "1_1") (pintype "passive"))
      (node (ref "C6") (pin "2") (pinfunction "2_2") (pintype "passive"))
      (node (ref "C7") (pin "1") (pinfunction "1_1") (pintype "passive"))
      (node (ref "C8") (pin "2") (pinfunction "2_2") (pintype "passive"))
      (node (ref "C9") (pin "1") (pinfunction "1_1") (pintype "passive"))
      (node (ref "DA1") (pin "8") (pinfunction "GND_8") (pintype "power_in"))
      (node (ref "DA2") (pin "8") (pinfunction "GND_8") (pintype "power_in"))
      (node (ref "DA3") (pin "8") (pinfunction "GND_8") (pintype "power_in"))
      (node (ref "IC10") (pin "5") (pinfunction "AGND_5") (pintype "power_in"))
      (node (ref "IC11") (pin "5") (pinfunction "AGND_5") (pintype "power_in"))
      (node (ref "IC2") (pin "10") (pinfunction "+IN_10") (pintype "input"))
      (node (ref "IC2") (pin "12") (pinfunction "+IN_12") (pintype "input"))
      (node (ref "IC2") (pin "3") (pinfunction "+IN_3") (pintype "input"))
      (node (ref "IC3") (pin "3") (pinfunction "+IN_3") (pintype "input"))
      (node (ref "IC3") (pin "5") (pinfunction "+IN_5") (pintype "input"))
      (node (ref "IC4") (pin "10") (pinfunction "+IN_10") (pintype "input"))
      (node (ref "IC4") (pin "12") (pinfunction "+IN_12") (pintype "input"))
      (node (ref "IC4") (pin "3") (pinfunction "+IN_3") (pintype "input"))
      (node (ref "IC4") (pin "5") (pinfunction "+IN_5") (pintype "input"))
      (node (ref "IC7") (pin "10") (pinfunction "+IN_10") (pintype "input"))
      (node (ref "IC7") (pin "12") (pinfunction "+IN_12") (pintype "input"))
      (node (ref "IC7") (pin "3") (pinfunction "+IN_3") (pintype "input"))
      (node (ref "IC7") (pin "5") (pinfunction "+IN_5") (pintype "input"))
      (node (ref "IC8") (pin "5") (pinfunction "AGND_5") (pintype "power_in"))
      (node (ref "IC9") (pin "5") (pinfunction "AGND_5") (pintype "power_in"))
      (node (ref "R12") (pin "1") (pinfunction "1_1") (pintype "passive"))
      (node (ref "R15") (pin "1") (pinfunction "1_1") (pintype "passive"))
      (node (ref "R18") (pin "1") (pinfunction "1_1") (pintype "passive"))
      (node (ref "R21") (pin "1") (pinfunction "1_1") (pintype "passive"))
      (node (ref "R24") (pin "1") (pinfunction "1_1") (pintype "passive"))
      (node (ref "R27") (pin "1") (pinfunction "1_1") (pintype "passive"))
      (node (ref "R3") (pin "1") (pinfunction "1_1") (pintype "passive"))
      (node (ref "R30") (pin "1") (pinfunction "1_1") (pintype "passive"))
      (node (ref "R33") (pin "1") (pinfunction "1_1") (pintype "passive"))
      (node (ref "R36") (pin "1") (pinfunction "1_1") (pintype "passive"))
      (node (ref "R46") (pin "2") (pinfunction "2_2") (pintype "passive"))
      (node (ref "R47") (pin "2") (pinfunction "2_2") (pintype "passive"))
      (node (ref "R49") (pin "2") (pinfunction "2_2") (pintype "passive"))
      (node (ref "R6") (pin "1") (pinfunction "1_1") (pintype "passive"))
      (node (ref "R73") (pin "1") (pinfunction "1_1") (pintype "passive"))
      (node (ref "R74") (pin "1") (pinfunction "1_1") (pintype "passive"))
      (node (ref "R75") (pin "1") (pinfunction "1_1") (pintype "passive"))
      (node (ref "R76") (pin "1") (pinfunction "1_1") (pintype "passive"))
      (node (ref "R78") (pin "2") (pinfunction "2_2") (pintype "passive"))
      (node (ref "R9") (pin "1") (pinfunction "1_1") (pintype "passive"))
      (node (ref "U$2") (pin "7") (pinfunction "7_7") (pintype "passive"))
    )
    (net (code "103") (name "Net-(C13-Pad2)") (class "Default")
      (node (ref "C13") (pin "2") (pinfunction "2_2") (pintype "passive"))
      (node (ref "R38") (pin "1") (pinfunction "1_1") (pintype "passive"))
    )
    (net (code "104") (name "Net-(C14-Pad2)") (class "Default")
      (node (ref "C14") (pin "2") (pinfunction "2_2") (pintype "passive"))
      (node (ref "R39") (pin "1") (pinfunction "1_1") (pintype "passive"))
    )
    (net (code "105") (name "Net-(C15-Pad2)") (class "Default")
      (node (ref "C15") (pin "2") (pinfunction "2_2") (pintype "passive"))
      (node (ref "R40") (pin "1") (pinfunction "1_1") (pintype "passive"))
    )
    (net (code "106") (name "Net-(DA1B-CV2)") (class "Default")
      (node (ref "DA1") (pin "6") (pinfunction "CV2_6") (pintype "input"))
      (node (ref "R29") (pin "2") (pinfunction "2_2") (pintype "passive"))
      (node (ref "R30") (pin "2") (pinfunction "2_2") (pintype "passive"))
    )
    (net (code "107") (name "Net-(DA1B-CV3)") (class "Default")
      (node (ref "DA1") (pin "11") (pinfunction "CV3_11") (pintype "input"))
      (node (ref "R32") (pin "2") (pinfunction "2_2") (pintype "passive"))
      (node (ref "R33") (pin "2") (pinfunction "2_2") (pintype "passive"))
    )
    (net (code "108") (name "Net-(DA1B-CV4)") (class "Default")
      (node (ref "DA1") (pin "14") (pinfunction "CV4_14") (pintype "input"))
      (node (ref "R35") (pin "2") (pinfunction "2_2") (pintype "passive"))
      (node (ref "R36") (pin "2") (pinfunction "2_2") (pintype "passive"))
    )
    (net (code "109") (name "Net-(DA1B-OUT1)") (class "Default")
      (node (ref "DA1") (pin "4") (pinfunction "OUT1_4") (pintype "output"))
      (node (ref "IC7") (pin "13") (pinfunction "-IN_13") (pintype "input"))
      (node (ref "R51") (pin "2") (pinfunction "2_2") (pintype "passive"))
    )
    (net (code "110") (name "Net-(DA1B-OUT2)") (class "Default")
      (node (ref "DA1") (pin "5") (pinfunction "OUT2_5") (pintype "output"))
      (node (ref "IC2") (pin "9") (pinfunction "-IN_9") (pintype "input"))
      (node (ref "R50") (pin "2") (pinfunction "2_2") (pintype "passive"))
      (node (ref "R69") (pin "1") (pinfunction "1_1") (pintype "passive"))
      (node (ref "R71") (pin "1") (pinfunction "1_1") (pintype "passive"))
    )
    (net (code "111") (name "Net-(DA1B-OUT3)") (class "Default")
      (node (ref "DA1") (pin "12") (pinfunction "OUT3_12") (pintype "output"))
      (node (ref "IC2") (pin "6") (pinfunction "-IN_6") (pintype "input"))
      (node (ref "R52") (pin "2") (pinfunction "2_2") (pintype "passive"))
    )
    (net (code "112") (name "Net-(DA1B-OUT4)") (class "Default")
      (node (ref "DA1") (pin "13") (pinfunction "OUT4_13") (pintype "output"))
      (node (ref "IC2") (pin "5") (pinfunction "+IN_5") (pintype "input"))
      (node (ref "R49") (pin "1") (pinfunction "1_1") (pintype "passive"))
    )
    (net (code "113") (name "Net-(DA1B-VREF)") (class "Default")
      (node (ref "DA1") (pin "1") (pinfunction "VREF_1") (pintype "output"))
      (node (ref "R40") (pin "2") (pinfunction "2_2") (pintype "passive"))
    )
    (net (code "114") (name "Net-(DA2B-CV2)") (class "Default")
      (node (ref "DA2") (pin "6") (pinfunction "CV2_6") (pintype "input"))
      (node (ref "R5") (pin "2") (pinfunction "2_2") (pintype "passive"))
      (node (ref "R6") (pin "2") (pinfunction "2_2") (pintype "passive"))
    )
    (net (code "115") (name "Net-(DA2B-CV3)") (class "Default")
      (node (ref "DA2") (pin "11") (pinfunction "CV3_11") (pintype "input"))
      (node (ref "R8") (pin "2") (pinfunction "2_2") (pintype "passive"))
      (node (ref "R9") (pin "2") (pinfunction "2_2") (pintype "passive"))
    )
    (net (code "116") (name "Net-(DA2B-CV4)") (class "Default")
      (node (ref "DA2") (pin "14") (pinfunction "CV4_14") (pintype "input"))
      (node (ref "R11") (pin "2") (pinfunction "2_2") (pintype "passive"))
      (node (ref "R12") (pin "2") (pinfunction "2_2") (pintype "passive"))
    )
    (net (code "117") (name "Net-(DA2B-VREF)") (class "Default")
      (node (ref "DA2") (pin "1") (pinfunction "VREF_1") (pintype "output"))
      (node (ref "R38") (pin "2") (pinfunction "2_2") (pintype "passive"))
    )
    (net (code "118") (name "Net-(DA3B-CV2)") (class "Default")
      (node (ref "DA3") (pin "6") (pinfunction "CV2_6") (pintype "input"))
      (node (ref "R17") (pin "2") (pinfunction "2_2") (pintype "passive"))
      (node (ref "R18") (pin "2") (pinfunction "2_2") (pintype "passive"))
    )
    (net (code "119") (name "Net-(DA3B-CV3)") (class "Default")
      (node (ref "DA3") (pin "11") (pinfunction "CV3_11") (pintype "input"))
      (node (ref "R20") (pin "2") (pinfunction "2_2") (pintype "passive"))
      (node (ref "R21") (pin "2") (pinfunction "2_2") (pintype "passive"))
    )
    (net (code "120") (name "Net-(DA3B-CV4)") (class "Default")
      (node (ref "DA3") (pin "14") (pinfunction "CV4_14") (pintype "input"))
      (node (ref "R23") (pin "2") (pinfunction "2_2") (pintype "passive"))
      (node (ref "R24") (pin "2") (pinfunction "2_2") (pintype "passive"))
    )
    (net (code "121") (name "Net-(DA3B-OUT2)") (class "Default")
      (node (ref "DA3") (pin "5") (pinfunction "OUT2_5") (pintype "output"))
      (node (ref "IC6") (pin "3") (pinfunction "+IN_3") (pintype "input"))
      (node (ref "R46") (pin "1") (pinfunction "1_1") (pintype "passive"))
    )
    (net (code "122") (name "Net-(DA3B-VREF)") (class "Default")
      (node (ref "DA3") (pin "1") (pinfunction "VREF_1") (pintype "output"))
      (node (ref "R39") (pin "2") (pinfunction "2_2") (pintype "passive"))
    )
    (net (code "123") (name "Net-(IC7A--IN)") (class "Default")
      (node (ref "IC7") (pin "1") (pinfunction "OUT_1") (pintype "output"))
      (node (ref "IC7") (pin "2") (pinfunction "-IN_2") (pintype "input"))
    )
    (net (code "124") (name "Net-(IC7D-OUT)") (class "Default")
      (node (ref "IC7") (pin "14") (pinfunction "OUT_14") (pintype "output"))
      (node (ref "R51") (pin "1") (pinfunction "1_1") (pintype "passive"))
      (node (ref "R71") (pin "2") (pinfunction "2_2") (pintype "passive"))
    )
    (net (code "125") (name "unconnected-(IC1-~{INT}-Pad1)") (class "Default")
      (node (ref "IC1") (pin "1") (pinfunction "~{INT}_1") (pintype "bidirectional"))
    )
  )
)
